# microcontroller_interface.net
KiCad netlist of a schematic drawn in Altium Designer
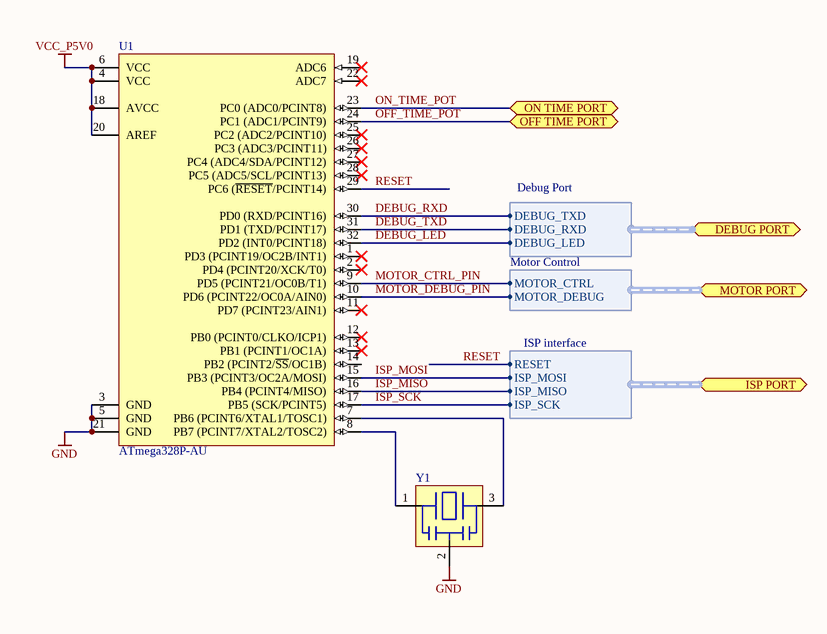
[diagram p0: microcontroller interface.SchDoc]

(export (version "E")
  (design (tool "Eeschema 10.0.6"))
  (components
    (comp (ref "U1")
      (value "ATmega328P-AU")
      (footprint "32A_N")
      (fields (field (name "PUBLISHER") "Altium Limited"))
      (libsource (lib "Atmel Microcontroller 8-Bit megaAVR") (part "ATmega328P-AU"))
    )
    (comp (ref "Y1")
      (value "CSTCE16M0V53")
      (footprint "CSTCE_V_C")
      (description "Ceremic Resonator, 16 MHz, Built-in capacitance 15pF, SMT, 5% tolerance")
      (libsource (lib "Murata Resonator") (part "CSTCE16M0V53"))
    )
  )
  (nets
    (net (code "7") (name "/DEBUG_LED") (class "Default")
      (node (ref "U1") (pin "32") (pinfunction "PD2_(INT0/PCINT18)_32") (pintype "bidirectional"))
    )
    (net (code "8") (name "/DEBUG_RXD") (class "Default")
      (node (ref "U1") (pin "30") (pinfunction "PD0_(RXD/PCINT16)_30") (pintype "bidirectional"))
    )
    (net (code "9") (name "/DEBUG_TXD") (class "Default")
      (node (ref "U1") (pin "31") (pinfunction "PD1_(TXD/PCINT17)_31") (pintype "bidirectional"))
    )
    (net (code "10") (name "/ISP_MISO") (class "Default")
      (node (ref "U1") (pin "16") (pinfunction "PB4_(PCINT4/MISO)_16") (pintype "bidirectional"))
    )
    (net (code "11") (name "/ISP_MOSI") (class "Default")
      (node (ref "U1") (pin "15") (pinfunction "PB3_(PCINT3/OC2A/MOSI)_15") (pintype "bidirectional"))
    )
    (net (code "12") (name "/ISP_SCK") (class "Default")
      (node (ref "U1") (pin "17") (pinfunction "PB5_(SCK/PCINT5)_17") (pintype "bidirectional"))
    )
    (net (code "13") (name "/MOTOR_CTRL_PIN") (class "Default")
      (node (ref "U1") (pin "9") (pinfunction "PD5_(PCINT21/OC0B/T1)_9") (pintype "bidirectional"))
    )
    (net (code "14") (name "/MOTOR_DEBUG_PIN") (class "Default")
      (node (ref "U1") (pin "10") (pinfunction "PD6_(PCINT22/OC0A/AIN0)_10") (pintype "bidirectional"))
    )
    (net (code "15") (name "/OFF_TIME_POT") (class "Default")
      (node (ref "U1") (pin "24") (pinfunction "PC1_(ADC1/PCINT9)_24") (pintype "bidirectional"))
    )
    (net (code "16") (name "/ON_TIME_POT") (class "Default")
      (node (ref "U1") (pin "23") (pinfunction "PC0_(ADC0/PCINT8)_23") (pintype "bidirectional"))
    )
    (net (code "17") (name "/RESET") (class "Default")
      (node (ref "U1") (pin "29") (pinfunction "PC6_(~{RESET}/PCINT14)_29") (pintype "bidirectional"))
    )
    (net (code "21") (name "GND") (class "Default")
      (node (ref "U1") (pin "21") (pinfunction "GND_21") (pintype "power_in"))
      (node (ref "U1") (pin "3") (pinfunction "GND_3") (pintype "power_in"))
      (node (ref "U1") (pin "5") (pinfunction "GND_5") (pintype "power_in"))
      (node (ref "Y1") (pin "2") (pinfunction "2_2") (pintype "passive"))
    )
    (net (code "22") (name "Net-(U1-PB6_(PCINT6{slash}XTAL1{slash}TOSC1))") (class "Default")
      (node (ref "U1") (pin "7") (pinfunction "PB6_(PCINT6/XTAL1/TOSC1)_7") (pintype "bidirectional"))
      (node (ref "Y1") (pin "3") (pinfunction "3_3") (pintype "passive"))
    )
    (net (code "23") (name "Net-(U1-PB7_(PCINT7{slash}XTAL2{slash}TOSC2))") (class "Default")
      (node (ref "U1") (pin "8") (pinfunction "PB7_(PCINT7/XTAL2/TOSC2)_8") (pintype "bidirectional"))
      (node (ref "Y1") (pin "1") (pinfunction "1_1") (pintype "passive"))
    )
    (net (code "24") (name "VCC_P5V0") (class "Default")
      (node (ref "U1") (pin "18") (pinfunction "AVCC_18") (pintype "power_in"))
      (node (ref "U1") (pin "20") (pinfunction "AREF_20") (pintype "passive"))
      (node (ref "U1") (pin "4") (pinfunction "VCC_4") (pintype "power_in"))
      (node (ref "U1") (pin "6") (pinfunction "VCC_6") (pintype "power_in"))
    )
    (net (code "25") (name "unconnected-(U1-ADC6-Pad19)") (class "Default")
      (node (ref "U1") (pin "19") (pinfunction "ADC6_19") (pintype "input+no_connect"))
    )
    (net (code "26") (name "unconnected-(U1-ADC7-Pad22)") (class "Default")
      (node (ref "U1") (pin "22") (pinfunction "ADC7_22") (pintype "input+no_connect"))
    )
    (net (code "27") (name "unconnected-(U1-PB0_(PCINT0{slash}CLKO{slash}ICP1)-Pad12)") (class "Default")
      (node (ref "U1") (pin "12") (pinfunction "PB0_(PCINT0/CLKO/ICP1)_12") (pintype "bidirectional+no_connect"))
    )
    (net (code "28") (name "unconnected-(U1-PB1_(PCINT1{slash}OC1A)-Pad13)") (class "Default")
      (node (ref "U1") (pin "13") (pinfunction "PB1_(PCINT1/OC1A)_13") (pintype "bidirectional+no_connect"))
    )
    (net (code "29") (name "unconnected-(U1-PB2_(PCINT2{slash}~{SS}{slash}OC1B)-Pad14)") (class "Default")
      (node (ref "U1") (pin "14") (pinfunction "PB2_(PCINT2/~{SS}/OC1B)_14") (pintype "bidirectional"))
    )
    (net (code "30") (name "unconnected-(U1-PC2_(ADC2{slash}PCINT10)-Pad25)") (class "Default")
      (node (ref "U1") (pin "25") (pinfunction "PC2_(ADC2/PCINT10)_25") (pintype "bidirectional+no_connect"))
    )
    (net (code "31") (name "unconnected-(U1-PC3_(ADC3{slash}PCINT11)-Pad26)") (class "Default")
      (node (ref "U1") (pin "26") (pinfunction "PC3_(ADC3/PCINT11)_26") (pintype "bidirectional+no_connect"))
    )
    (net (code "32") (name "unconnected-(U1-PC4_(ADC4{slash}SDA{slash}PCINT12)-Pad27)") (class "Default")
      (node (ref "U1") (pin "27") (pinfunction "PC4_(ADC4/SDA/PCINT12)_27") (pintype "bidirectional+no_connect"))
    )
    (net (code "33") (name "unconnected-(U1-PC5_(ADC5{slash}SCL{slash}PCINT13)-Pad28)") (class "Default")
      (node (ref "U1") (pin "28") (pinfunction "PC5_(ADC5/SCL/PCINT13)_28") (pintype "bidirectional+no_connect"))
    )
    (net (code "34") (name "unconnected-(U1-PD3_(PCINT19{slash}OC2B{slash}INT1)-Pad1)") (class "Default")
      (node (ref "U1") (pin "1") (pinfunction "PD3_(PCINT19/OC2B/INT1)_1") (pintype "bidirectional+no_connect"))
    )
    (net (code "35") (name "unconnected-(U1-PD4_(PCINT20{slash}XCK{slash}T0)-Pad2)") (class "Default")
      (node (ref "U1") (pin "2") (pinfunction "PD4_(PCINT20/XCK/T0)_2") (pintype "bidirectional+no_connect"))
    )
    (net (code "36") (name "unconnected-(U1-PD7_(PCINT23{slash}AIN1)-Pad11)") (class "Default")
      (node (ref "U1") (pin "11") (pinfunction "PD7_(PCINT23/AIN1)_11") (pintype "bidirectional+no_connect"))
    )
  )
)
